# openSX70_RAW_NEW_LAYOUT_20171220.net
KiCad netlist of a schematic drawn in EAGLE
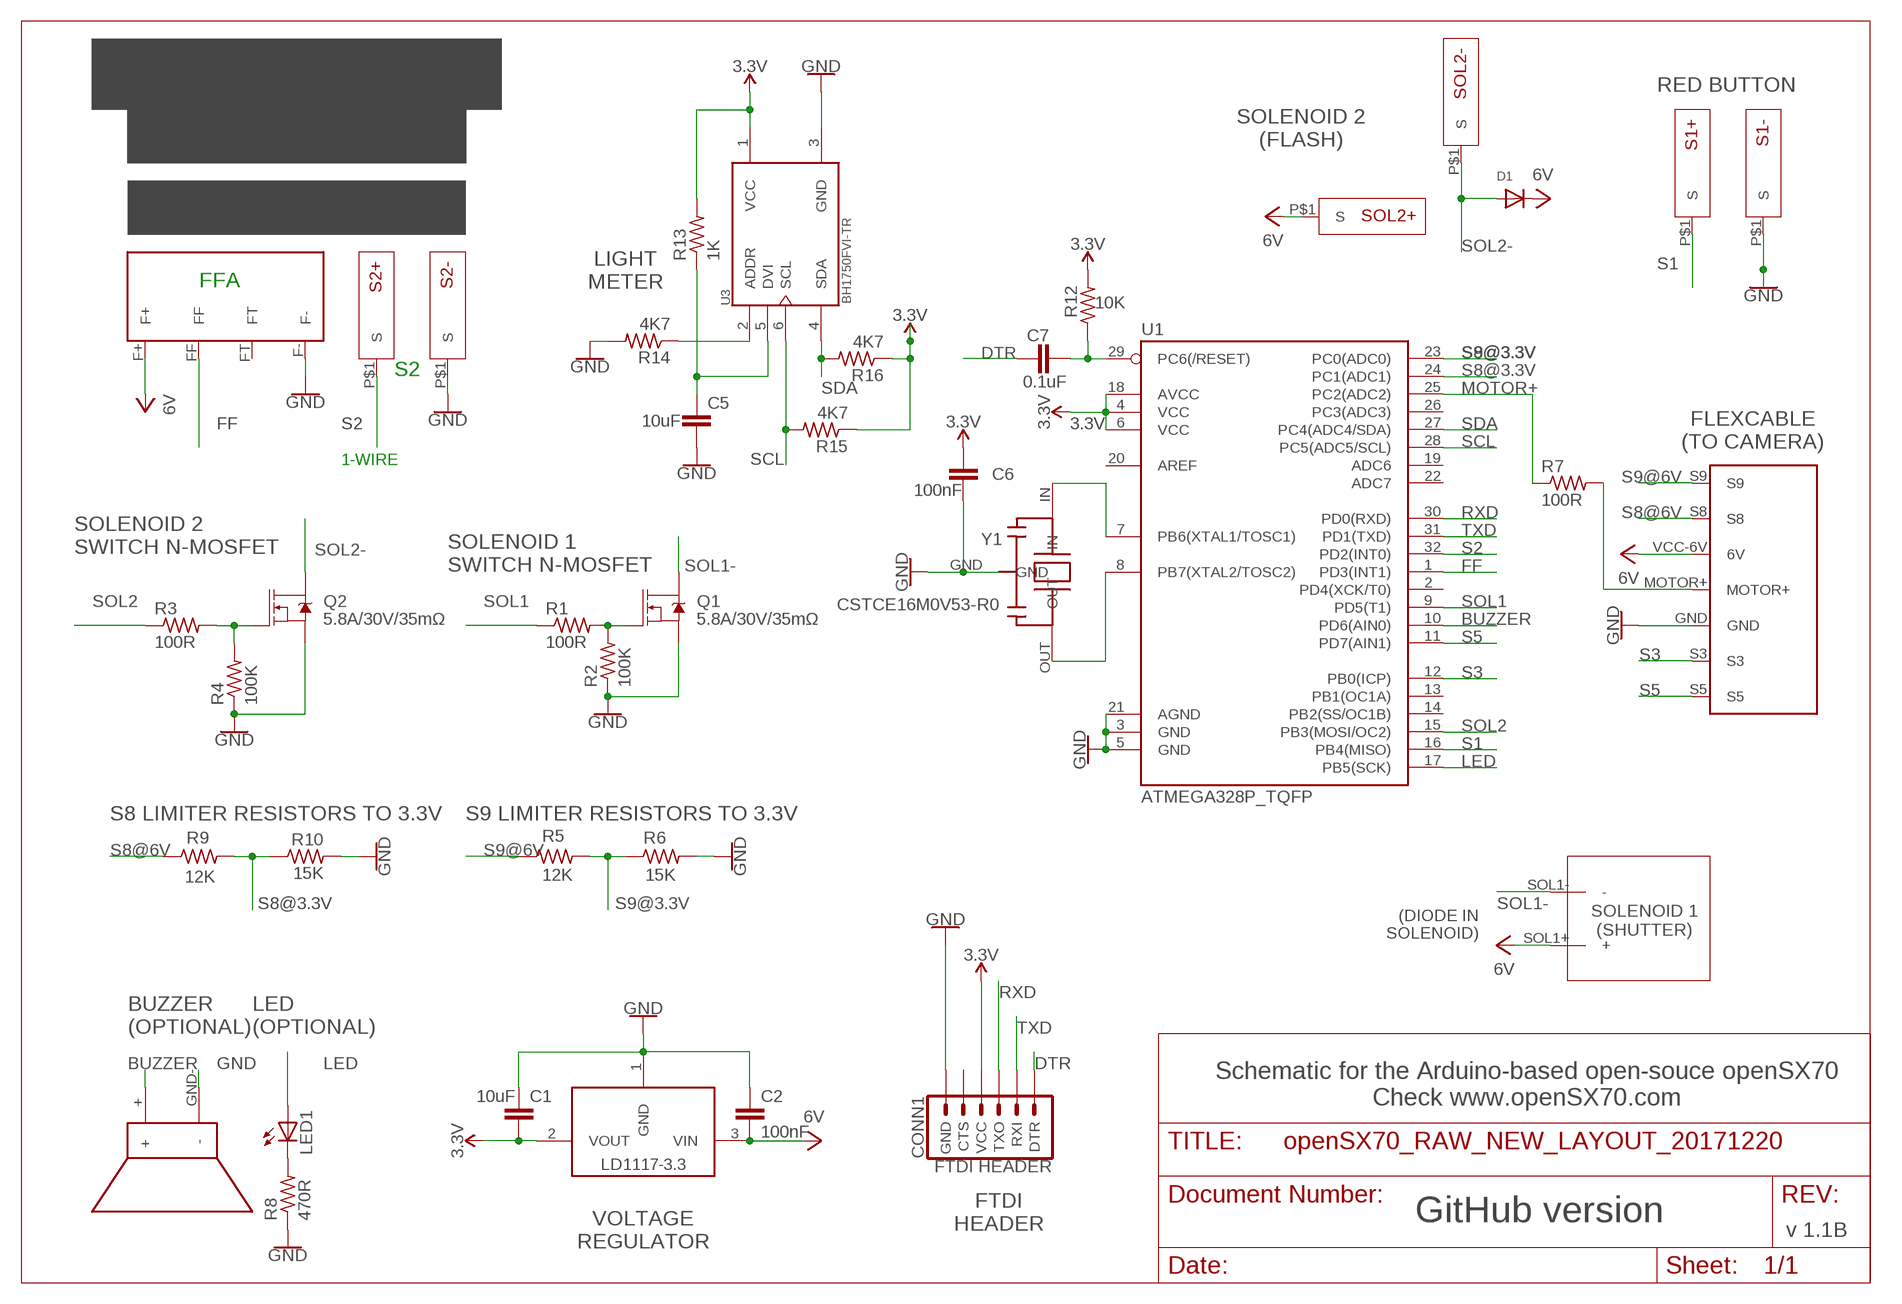
[diagram p0: schematic, sheet 1]

(export (version "E")
  (design (tool "Eeschema 10.0.6"))
  (components
    (comp (ref "BUZZ1")
      (value "CSET8-5G")
      (footprint "eagle-import:CSET8-5G_PACKAGE")
      (libsource (lib "eagle-import") (part "CSET8-5G"))
    )
    (comp (ref "C1")
      (value "10uF")
      (footprint "eagle-import:0603")
      (libsource (lib "eagle-import") (part "10UF-0603-6.3V-20%"))
    )
    (comp (ref "C2")
      (value "100nF")
      (footprint "eagle-import:C0603K")
      (libsource (lib "eagle-import") (part "C-EUC0603K"))
    )
    (comp (ref "C5")
      (value "10uF")
      (footprint "eagle-import:0603")
      (libsource (lib "eagle-import") (part "10UF-0603-6.3V-20%"))
    )
    (comp (ref "C6")
      (value "100nF")
      (footprint "eagle-import:C0805")
      (libsource (lib "eagle-import") (part "resistor_C-EUC0805"))
    )
    (comp (ref "C7")
      (value "0.1uF")
      (footprint "eagle-import:0603")
      (libsource (lib "eagle-import") (part "0.1UF-0603-25V-(+80/-20%)"))
    )
    (comp (ref "CONN1")
      (value "FTDI HEADER")
      (footprint "eagle-import:1X06")
      (libsource (lib "eagle-import") (part "6_PIN_SERIAL_TARGET"))
    )
    (comp (ref "D1")
      (value "DIODESOD-523")
      (footprint "eagle-import:SOD-523")
      (libsource (lib "eagle-import") (part "DIODESOD-523"))
    )
    (comp (ref "LD11173.3V")
      (value "LD1117 3.3V")
      (footprint "eagle-import:SOT223")
      (fields (field (name "MF") "Advanced Monolithic Systems") (field (name "MP") "AMS1117-5.0"))
      (libsource (lib "eagle-import") (part "LD1117-3.3"))
    )
    (comp (ref "LED1")
      (value "LEDCHIPLED_0805")
      (footprint "eagle-import:CHIPLED_0805")
      (libsource (lib "eagle-import") (part "LEDCHIPLED_0805"))
    )
    (comp (ref "Q1")
      (value "5.8A/30V/35mΩ")
      (footprint "eagle-import:SOT23-3")
      (libsource (lib "eagle-import") (part "MOSFET-NCH-AO3404A"))
    )
    (comp (ref "Q2")
      (value "5.8A/30V/35mΩ")
      (footprint "eagle-import:SOT23-3")
      (libsource (lib "eagle-import") (part "MOSFET-NCH-AO3404A"))
    )
    (comp (ref "R1")
      (value "100R")
      (footprint "eagle-import:R0603")
      (libsource (lib "eagle-import") (part "R-US_R0603"))
    )
    (comp (ref "R2")
      (value "100K")
      (footprint "eagle-import:R0603")
      (libsource (lib "eagle-import") (part "R-US_R0603"))
    )
    (comp (ref "R3")
      (value "100R")
      (footprint "eagle-import:R0603")
      (libsource (lib "eagle-import") (part "R-US_R0603"))
    )
    (comp (ref "R4")
      (value "100K")
      (footprint "eagle-import:R0603")
      (libsource (lib "eagle-import") (part "R-US_R0603"))
    )
    (comp (ref "R5")
      (value "12K")
      (footprint "eagle-import:R0603")
      (libsource (lib "eagle-import") (part "R-US_R0603"))
    )
    (comp (ref "R6")
      (value "15K")
      (footprint "eagle-import:R0603")
      (libsource (lib "eagle-import") (part "R-US_R0603"))
    )
    (comp (ref "R7")
      (value "100R")
      (footprint "eagle-import:R0603")
      (libsource (lib "eagle-import") (part "R-US_R0603"))
    )
    (comp (ref "R8")
      (value "470R")
      (footprint "eagle-import:R0603")
      (libsource (lib "eagle-import") (part "R-US_R0603"))
    )
    (comp (ref "R9")
      (value "12K")
      (footprint "eagle-import:R0603")
      (libsource (lib "eagle-import") (part "R-US_R0603"))
    )
    (comp (ref "R10")
      (value "15K")
      (footprint "eagle-import:R0603")
      (libsource (lib "eagle-import") (part "R-US_R0603"))
    )
    (comp (ref "R12")
      (value "10K")
      (footprint "eagle-import:R0603")
      (libsource (lib "eagle-import") (part "R-US_R0603"))
    )
    (comp (ref "R13")
      (value "1K")
      (footprint "eagle-import:R0603")
      (libsource (lib "eagle-import") (part "R-US_R0603"))
    )
    (comp (ref "R14")
      (value "4K7")
      (footprint "eagle-import:R0603")
      (libsource (lib "eagle-import") (part "R-US_R0603"))
    )
    (comp (ref "R15")
      (value "4K7")
      (footprint "eagle-import:R0603")
      (libsource (lib "eagle-import") (part "R-US_R0603"))
    )
    (comp (ref "R16")
      (value "4K7")
      (footprint "eagle-import:R0603")
      (libsource (lib "eagle-import") (part "R-US_R0603"))
    )
    (comp (ref "S1+")
      (value "SX70_S-PAD")
      (footprint "eagle-import:SX70-S-PAD")
      (libsource (lib "eagle-import") (part "SX70_S-PAD"))
    )
    (comp (ref "S1-")
      (value "SX70_S-PAD")
      (footprint "eagle-import:SX70-S-PAD")
      (libsource (lib "eagle-import") (part "SX70_S-PAD"))
    )
    (comp (ref "S2+")
      (value "SX70_S-PAD")
      (footprint "eagle-import:SX70-S-PAD")
      (libsource (lib "eagle-import") (part "SX70_S-PAD"))
    )
    (comp (ref "S2-")
      (value "SX70_S-PAD")
      (footprint "eagle-import:SX70-S-PAD")
      (libsource (lib "eagle-import") (part "SX70_S-PAD"))
    )
    (comp (ref "SOL1")
      (value "SX70-SOLENOID1-2PADS")
      (footprint "eagle-import:SX70-SOLENOID1-2")
      (libsource (lib "eagle-import") (part "SX70-SOLENOID1-2PADS"))
    )
    (comp (ref "SOL2+")
      (value "SX70_S-PAD")
      (footprint "eagle-import:SX70-S-PAD")
      (libsource (lib "eagle-import") (part "SX70_S-PAD"))
    )
    (comp (ref "SOL2-")
      (value "SX70_S-PAD")
      (footprint "eagle-import:SX70-S-PAD")
      (libsource (lib "eagle-import") (part "SX70_S-PAD"))
    )
    (comp (ref "U$1")
      (value "SX70-7-PAD")
      (footprint "eagle-import:SX70-7-PAD")
      (libsource (lib "eagle-import") (part "SX70-7-PAD"))
    )
    (comp (ref "U$2")
      (value "FFA")
      (footprint "eagle-import:FFA-PAD-PACKAGE")
      (libsource (lib "eagle-import") (part "SX70-FFA-PAD"))
    )
    (comp (ref "U1")
      (value "ATMEGA328P_TQFP")
      (footprint "eagle-import:TQFP32-08")
      (libsource (lib "eagle-import") (part "ATMEGA328P_TQFP"))
    )
    (comp (ref "U3")
      (value "BH1750FVI-TR")
      (footprint "eagle-import:SOTFL50P300X75-6N")
      (fields (field (name "MF") "Rohm"))
      (libsource (lib "eagle-import") (part "BH1750FVI-TR"))
    )
    (comp (ref "Y1")
      (value "CSTCE16M0V53-R0")
      (footprint "eagle-import:CFP95P160X100-3N")
      (fields (field (name "MF") "Murata"))
      (libsource (lib "eagle-import") (part "CSTCE16M0V53-R0"))
    )
  )
  (nets
    (net (code "1") (name "/BUZZER") (class "Default")
      (node (ref "BUZZ1") (pin "+") (pinfunction "+_+") (pintype "bidirectional"))
      (node (ref "U1") (pin "10") (pinfunction "PD6(AIN0)_10") (pintype "bidirectional"))
    )
    (net (code "2") (name "/DTR") (class "Default")
      (node (ref "C7") (pin "1") (pinfunction "1_1") (pintype "passive"))
      (node (ref "CONN1") (pin "1") (pinfunction "DTR_1") (pintype "passive"))
    )
    (net (code "3") (name "/FF") (class "Default")
      (node (ref "U$2") (pin "FF") (pinfunction "FF_FF") (pintype "bidirectional"))
      (node (ref "U1") (pin "1") (pinfunction "PD3(INT1)_1") (pintype "bidirectional"))
    )
    (net (code "4") (name "/LED") (class "Default")
      (node (ref "LED1") (pin "A") (pinfunction "A_A") (pintype "passive"))
      (node (ref "U1") (pin "17") (pinfunction "PB5(SCK)_17") (pintype "bidirectional"))
    )
    (net (code "5") (name "/MOTOR+") (class "Default")
      (node (ref "R7") (pin "1") (pinfunction "1_1") (pintype "passive"))
      (node (ref "U1") (pin "25") (pinfunction "PC2(ADC2)_25") (pintype "bidirectional"))
    )
    (net (code "6") (name "/RXD") (class "Default")
      (node (ref "CONN1") (pin "3") (pinfunction "TXO_3") (pintype "passive"))
      (node (ref "U1") (pin "30") (pinfunction "PD0(RXD)_30") (pintype "bidirectional"))
    )
    (net (code "7") (name "/S1") (class "Default")
      (node (ref "S1+") (pin "P$1") (pinfunction "S_P$1") (pintype "bidirectional"))
      (node (ref "U1") (pin "16") (pinfunction "PB4(MISO)_16") (pintype "bidirectional"))
    )
    (net (code "8") (name "/S2") (class "Default")
      (node (ref "S2+") (pin "P$1") (pinfunction "S_P$1") (pintype "bidirectional"))
      (node (ref "U1") (pin "32") (pinfunction "PD2(INT0)_32") (pintype "bidirectional"))
    )
    (net (code "9") (name "/S3") (class "Default")
      (node (ref "U$1") (pin "S3") (pinfunction "S3_S3") (pintype "bidirectional"))
      (node (ref "U1") (pin "12") (pinfunction "PB0(ICP)_12") (pintype "bidirectional"))
    )
    (net (code "10") (name "/S5") (class "Default")
      (node (ref "U$1") (pin "S5") (pinfunction "S5_S5") (pintype "bidirectional"))
      (node (ref "U1") (pin "11") (pinfunction "PD7(AIN1)_11") (pintype "bidirectional"))
    )
    (net (code "11") (name "/S8@3.3V") (class "Default")
      (node (ref "R10") (pin "1") (pinfunction "1_1") (pintype "passive"))
      (node (ref "R9") (pin "2") (pinfunction "2_2") (pintype "passive"))
      (node (ref "U1") (pin "24") (pinfunction "PC1(ADC1)_24") (pintype "bidirectional"))
    )
    (net (code "12") (name "/S8@6V") (class "Default")
      (node (ref "R9") (pin "1") (pinfunction "1_1") (pintype "passive"))
      (node (ref "U$1") (pin "S8") (pinfunction "S8_S8") (pintype "bidirectional"))
    )
    (net (code "13") (name "/S9@3.3V") (class "Default")
      (node (ref "R5") (pin "2") (pinfunction "2_2") (pintype "passive"))
      (node (ref "R6") (pin "1") (pinfunction "1_1") (pintype "passive"))
      (node (ref "U1") (pin "23") (pinfunction "PC0(ADC0)_23") (pintype "bidirectional"))
    )
    (net (code "14") (name "/S9@6V") (class "Default")
      (node (ref "R5") (pin "1") (pinfunction "1_1") (pintype "passive"))
      (node (ref "U$1") (pin "S9") (pinfunction "S9_S9") (pintype "bidirectional"))
    )
    (net (code "15") (name "/SCL") (class "Default")
      (node (ref "R15") (pin "2") (pinfunction "2_2") (pintype "passive"))
      (node (ref "U1") (pin "28") (pinfunction "PC5(ADC5/SCL)_28") (pintype "bidirectional"))
      (node (ref "U3") (pin "6") (pinfunction "SCL_6") (pintype "input"))
    )
    (net (code "16") (name "/SDA") (class "Default")
      (node (ref "R16") (pin "2") (pinfunction "2_2") (pintype "passive"))
      (node (ref "U1") (pin "27") (pinfunction "PC4(ADC4/SDA)_27") (pintype "bidirectional"))
      (node (ref "U3") (pin "4") (pinfunction "SDA_4") (pintype "bidirectional"))
    )
    (net (code "17") (name "/SOL1") (class "Default")
      (node (ref "R1") (pin "1") (pinfunction "1_1") (pintype "passive"))
      (node (ref "U1") (pin "9") (pinfunction "PD5(T1)_9") (pintype "bidirectional"))
    )
    (net (code "18") (name "/SOL1-") (class "Default")
      (node (ref "Q1") (pin "3") (pinfunction "D_3") (pintype "bidirectional"))
      (node (ref "SOL1") (pin "SOL1-") (pinfunction "-_SOL1-") (pintype "bidirectional"))
    )
    (net (code "19") (name "/SOL2") (class "Default")
      (node (ref "R3") (pin "1") (pinfunction "1_1") (pintype "passive"))
      (node (ref "U1") (pin "15") (pinfunction "PB3(MOSI/OC2)_15") (pintype "bidirectional"))
    )
    (net (code "20") (name "/SOL2-") (class "Default")
      (node (ref "D1") (pin "A") (pinfunction "A_A") (pintype "passive"))
      (node (ref "Q2") (pin "3") (pinfunction "D_3") (pintype "bidirectional"))
      (node (ref "SOL2-") (pin "P$1") (pinfunction "S_P$1") (pintype "bidirectional"))
    )
    (net (code "21") (name "/TXD") (class "Default")
      (node (ref "CONN1") (pin "2") (pinfunction "RXI_2") (pintype "passive"))
      (node (ref "U1") (pin "31") (pinfunction "PD1(TXD)_31") (pintype "bidirectional"))
    )
    (net (code "22") (name "3.3V") (class "Default")
      (node (ref "C1") (pin "2") (pinfunction "2_2") (pintype "passive"))
      (node (ref "C6") (pin "1") (pinfunction "1_1") (pintype "passive"))
      (node (ref "CONN1") (pin "4") (pinfunction "VCC_4") (pintype "passive"))
      (node (ref "LD11173.3V") (pin "2") (pinfunction "VOUT_2") (pintype "bidirectional"))
      (node (ref "R12") (pin "2") (pinfunction "2_2") (pintype "passive"))
      (node (ref "R13") (pin "2") (pinfunction "2_2") (pintype "passive"))
      (node (ref "R15") (pin "1") (pinfunction "1_1") (pintype "passive"))
      (node (ref "R16") (pin "1") (pinfunction "1_1") (pintype "passive"))
      (node (ref "U1") (pin "18") (pinfunction "AVCC_18") (pintype "bidirectional"))
      (node (ref "U1") (pin "4") (pinfunction "VCC_4") (pintype "bidirectional"))
      (node (ref "U1") (pin "6") (pinfunction "VCC_6") (pintype "bidirectional"))
      (node (ref "U3") (pin "1") (pinfunction "VCC_1") (pintype "power_in"))
    )
    (net (code "23") (name "6V") (class "Default")
      (node (ref "C2") (pin "2") (pinfunction "2_2") (pintype "passive"))
      (node (ref "D1") (pin "K") (pinfunction "C_K") (pintype "passive"))
      (node (ref "LD11173.3V") (pin "3") (pinfunction "VIN_3") (pintype "bidirectional"))
      (node (ref "SOL1") (pin "SOL1+") (pinfunction "+_SOL1+") (pintype "bidirectional"))
      (node (ref "SOL2+") (pin "P$1") (pinfunction "S_P$1") (pintype "bidirectional"))
      (node (ref "U$1") (pin "VCC-6V") (pinfunction "6V_VCC-6V") (pintype "bidirectional"))
      (node (ref "U$2") (pin "F+") (pinfunction "F+_F+") (pintype "bidirectional"))
    )
    (net (code "24") (name "GND") (class "Default")
      (node (ref "BUZZ1") (pin "GND-") (pinfunction "-_GND-") (pintype "bidirectional"))
      (node (ref "C1") (pin "1") (pinfunction "1_1") (pintype "passive"))
      (node (ref "C2") (pin "1") (pinfunction "1_1") (pintype "passive"))
      (node (ref "C5") (pin "2") (pinfunction "2_2") (pintype "passive"))
      (node (ref "C6") (pin "2") (pinfunction "2_2") (pintype "passive"))
      (node (ref "CONN1") (pin "6") (pinfunction "GND_6") (pintype "passive"))
      (node (ref "LD11173.3V") (pin "1") (pinfunction "GND_1") (pintype "bidirectional"))
      (node (ref "Q1") (pin "2") (pinfunction "S_2") (pintype "bidirectional"))
      (node (ref "Q2") (pin "2") (pinfunction "S_2") (pintype "bidirectional"))
      (node (ref "R10") (pin "2") (pinfunction "2_2") (pintype "passive"))
      (node (ref "R14") (pin "2") (pinfunction "2_2") (pintype "passive"))
      (node (ref "R2") (pin "1") (pinfunction "1_1") (pintype "passive"))
      (node (ref "R4") (pin "1") (pinfunction "1_1") (pintype "passive"))
      (node (ref "R6") (pin "2") (pinfunction "2_2") (pintype "passive"))
      (node (ref "R8") (pin "1") (pinfunction "1_1") (pintype "passive"))
      (node (ref "S1-") (pin "P$1") (pinfunction "S_P$1") (pintype "bidirectional"))
      (node (ref "S2-") (pin "P$1") (pinfunction "S_P$1") (pintype "bidirectional"))
      (node (ref "U$1") (pin "GND") (pinfunction "GND_GND") (pintype "bidirectional"))
      (node (ref "U$2") (pin "F-") (pinfunction "F-_F-") (pintype "bidirectional"))
      (node (ref "U1") (pin "21") (pinfunction "AGND_21") (pintype "bidirectional"))
      (node (ref "U1") (pin "3") (pinfunction "GND_3") (pintype "bidirectional"))
      (node (ref "U1") (pin "5") (pinfunction "GND_5") (pintype "bidirectional"))
      (node (ref "U3") (pin "3") (pinfunction "GND_3") (pintype "power_in"))
      (node (ref "Y1") (pin "GND") (pinfunction "GND_GND") (pintype "passive"))
    )
    (net (code "25") (name "Net-(LED1-PadC)") (class "Default")
      (node (ref "LED1") (pin "C") (pinfunction "C_C") (pintype "passive"))
      (node (ref "R8") (pin "2") (pinfunction "2_2") (pintype "passive"))
    )
    (net (code "26") (name "Net-(Q1-G)") (class "Default")
      (node (ref "Q1") (pin "1") (pinfunction "G_1") (pintype "bidirectional"))
      (node (ref "R1") (pin "2") (pinfunction "2_2") (pintype "passive"))
      (node (ref "R2") (pin "2") (pinfunction "2_2") (pintype "passive"))
    )
    (net (code "27") (name "Net-(Q2-G)") (class "Default")
      (node (ref "Q2") (pin "1") (pinfunction "G_1") (pintype "bidirectional"))
      (node (ref "R3") (pin "2") (pinfunction "2_2") (pintype "passive"))
      (node (ref "R4") (pin "2") (pinfunction "2_2") (pintype "passive"))
    )
    (net (code "28") (name "Net-(R7-Pad2)") (class "Default")
      (node (ref "R7") (pin "2") (pinfunction "2_2") (pintype "passive"))
      (node (ref "U$1") (pin "MOTOR+") (pinfunction "MOTOR+_MOTOR+") (pintype "bidirectional"))
    )
    (net (code "29") (name "Net-(U1-PB6(XTAL1{slash}TOSC1))") (class "Default")
      (node (ref "U1") (pin "7") (pinfunction "PB6(XTAL1/TOSC1)_7") (pintype "bidirectional"))
      (node (ref "Y1") (pin "IN") (pinfunction "IN_IN") (pintype "input"))
    )
    (net (code "30") (name "Net-(U1-PB7(XTAL2{slash}TOSC2))") (class "Default")
      (node (ref "U1") (pin "8") (pinfunction "PB7(XTAL2/TOSC2)_8") (pintype "bidirectional"))
      (node (ref "Y1") (pin "OUT") (pinfunction "OUT_OUT") (pintype "output"))
    )
    (net (code "31") (name "Net-(U1-PC6({slash}RESET))") (class "Default")
      (node (ref "C7") (pin "2") (pinfunction "2_2") (pintype "passive"))
      (node (ref "R12") (pin "1") (pinfunction "1_1") (pintype "passive"))
      (node (ref "U1") (pin "29") (pinfunction "PC6(/RESET)_29") (pintype "bidirectional"))
    )
    (net (code "32") (name "Net-(U3-ADDR)") (class "Default")
      (node (ref "R14") (pin "1") (pinfunction "1_1") (pintype "passive"))
      (node (ref "U3") (pin "2") (pinfunction "ADDR_2") (pintype "input"))
    )
    (net (code "33") (name "Net-(U3-DVI)") (class "Default")
      (node (ref "C5") (pin "1") (pinfunction "1_1") (pintype "passive"))
      (node (ref "R13") (pin "1") (pinfunction "1_1") (pintype "passive"))
      (node (ref "U3") (pin "5") (pinfunction "DVI_5") (pintype "input"))
    )
    (net (code "34") (name "unconnected-(CONN1-CTS-Pad5)") (class "Default")
      (node (ref "CONN1") (pin "5") (pinfunction "CTS_5") (pintype "passive"))
    )
    (net (code "35") (name "unconnected-(U$2-PadFT)") (class "Default")
      (node (ref "U$2") (pin "FT") (pinfunction "FT_FT") (pintype "bidirectional"))
    )
    (net (code "36") (name "unconnected-(U1-ADC6-Pad19)") (class "Default")
      (node (ref "U1") (pin "19") (pinfunction "ADC6_19") (pintype "bidirectional"))
    )
    (net (code "37") (name "unconnected-(U1-ADC7-Pad22)") (class "Default")
      (node (ref "U1") (pin "22") (pinfunction "ADC7_22") (pintype "bidirectional"))
    )
    (net (code "38") (name "unconnected-(U1-AREF-Pad20)") (class "Default")
      (node (ref "U1") (pin "20") (pinfunction "AREF_20") (pintype "bidirectional"))
    )
    (net (code "39") (name "unconnected-(U1-PB1(OC1A)-Pad13)") (class "Default")
      (node (ref "U1") (pin "13") (pinfunction "PB1(OC1A)_13") (pintype "bidirectional"))
    )
    (net (code "40") (name "unconnected-(U1-PB2(SS{slash}OC1B)-Pad14)") (class "Default")
      (node (ref "U1") (pin "14") (pinfunction "PB2(SS/OC1B)_14") (pintype "bidirectional"))
    )
    (net (code "41") (name "unconnected-(U1-PC3(ADC3)-Pad26)") (class "Default")
      (node (ref "U1") (pin "26") (pinfunction "PC3(ADC3)_26") (pintype "bidirectional"))
    )
    (net (code "42") (name "unconnected-(U1-PD4(XCK{slash}T0)-Pad2)") (class "Default")
      (node (ref "U1") (pin "2") (pinfunction "PD4(XCK/T0)_2") (pintype "bidirectional"))
    )
  )
)
